# POWER_Management.net
KiCad netlist of a schematic drawn in Altium Designer
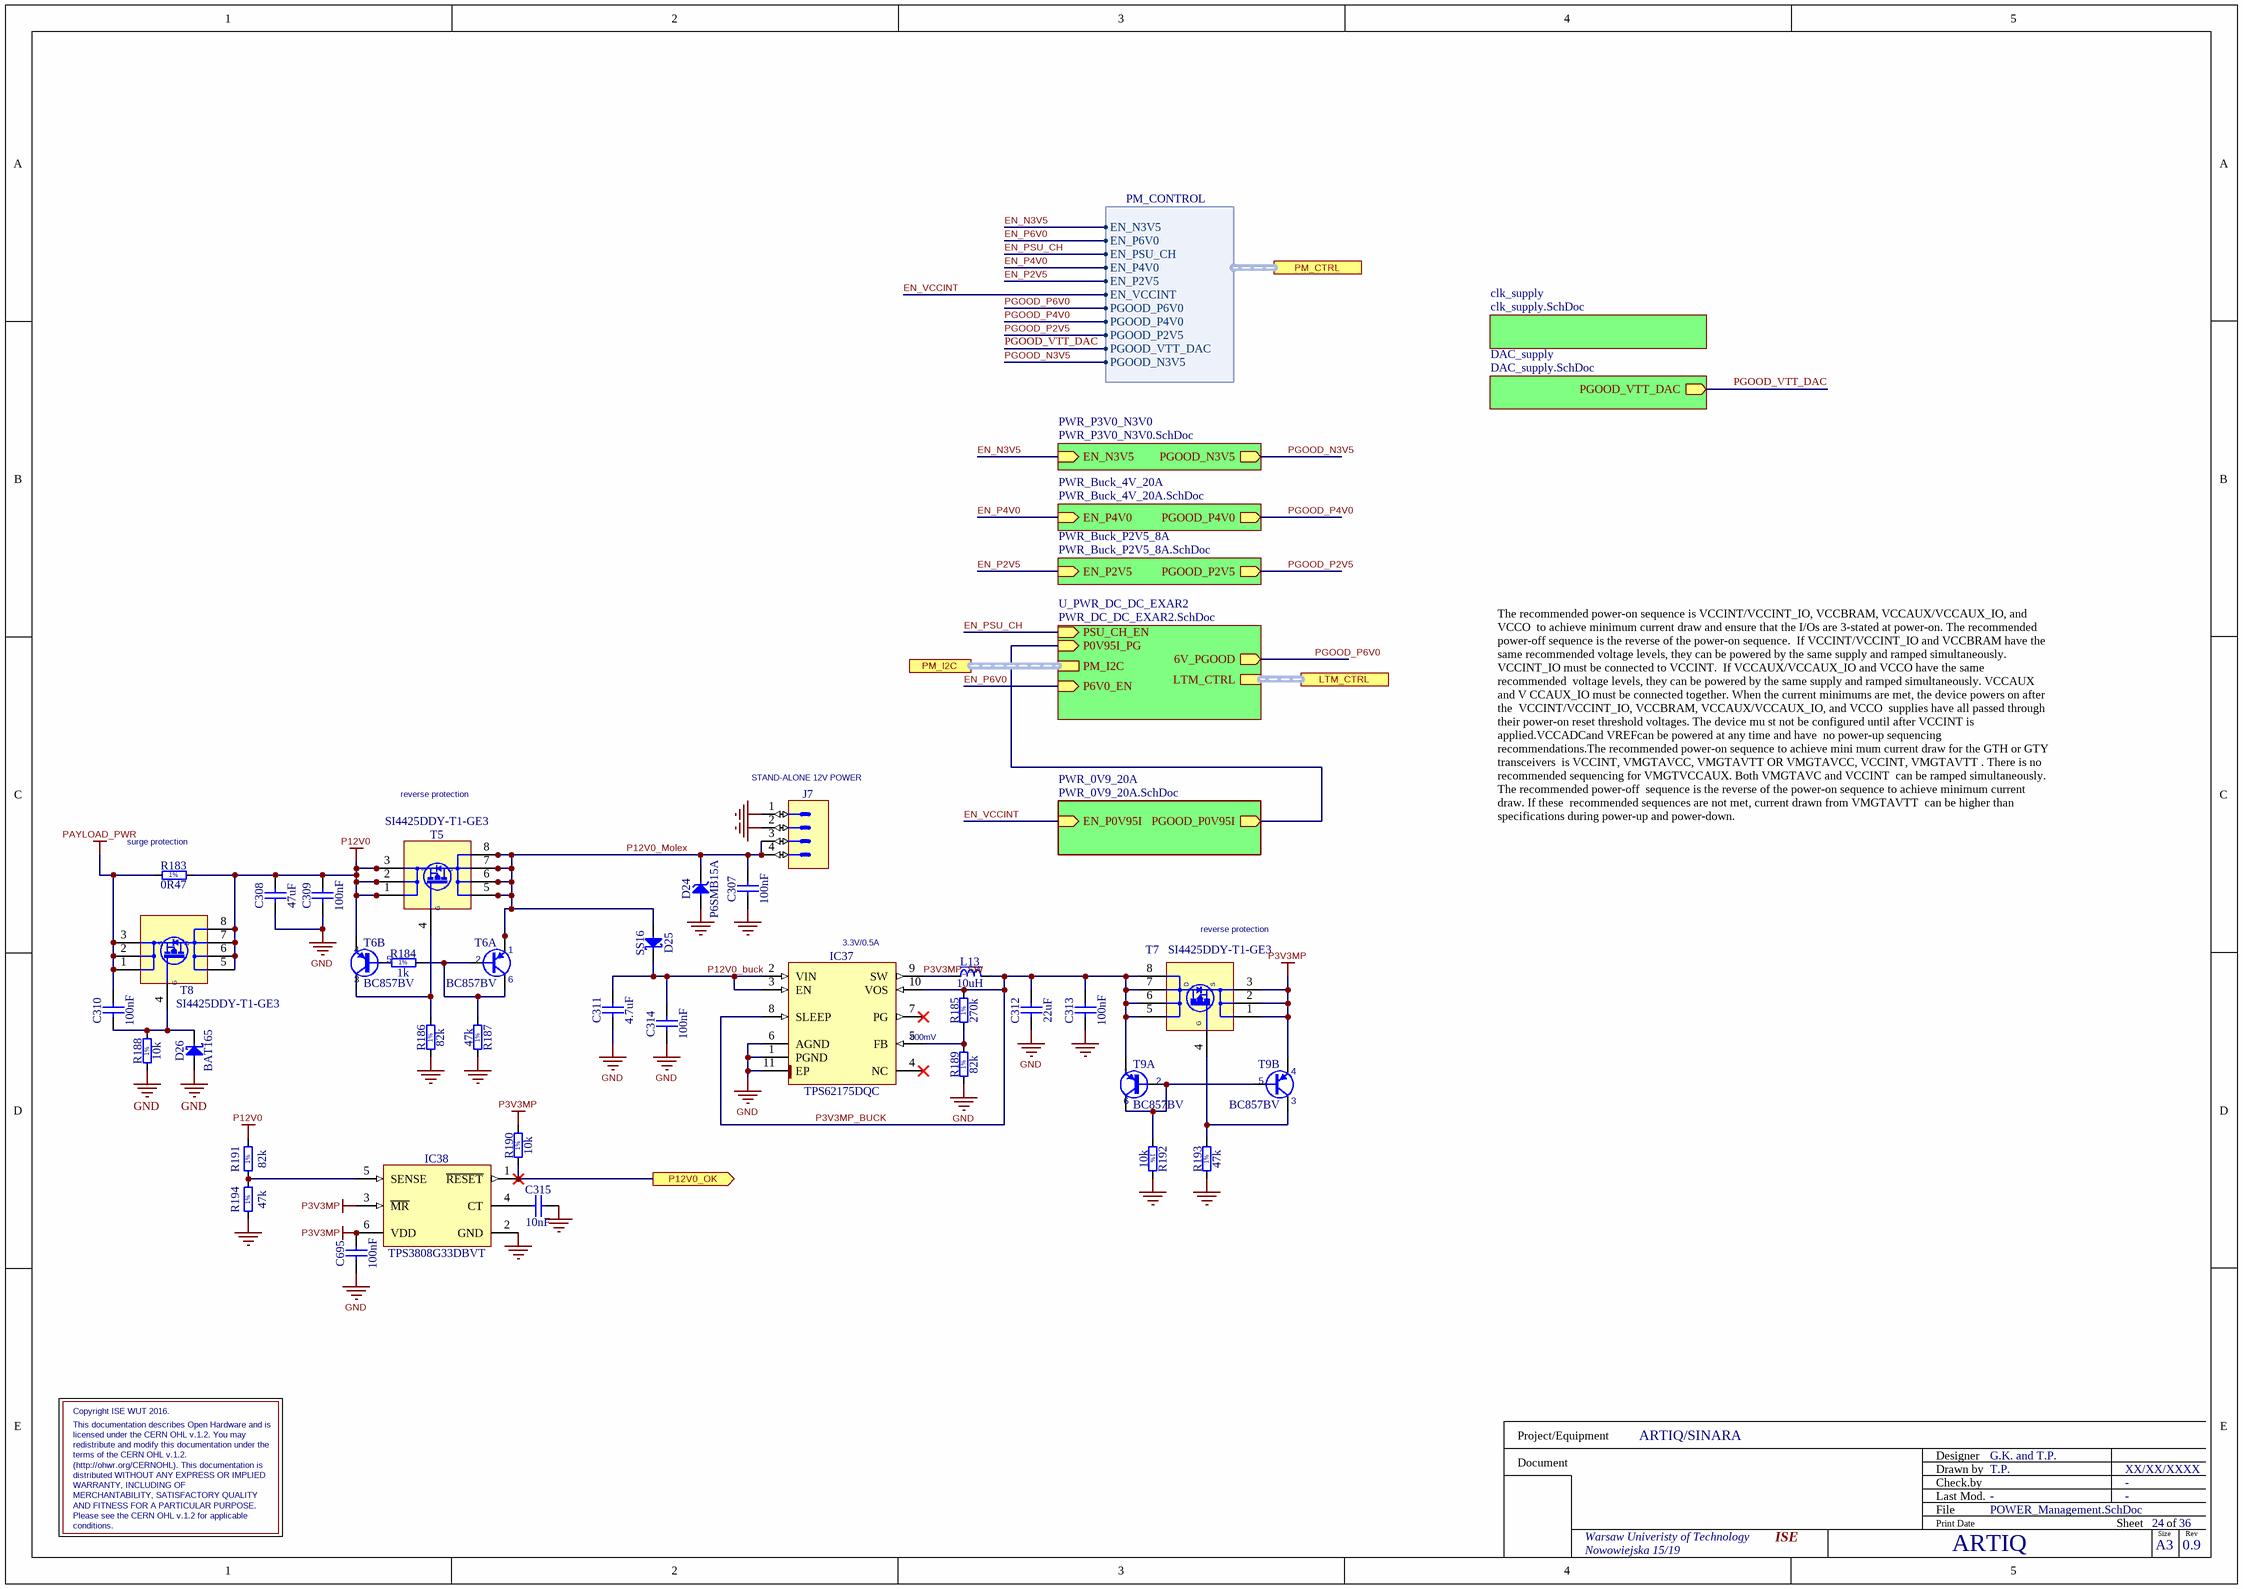
[diagram p0: POWER_Management.SchDoc]

(export (version "E")
  (design (tool "Eeschema 10.0.6"))
  (components
    (comp (ref "C307")
      (value "100nF")
      (footprint "CAPC1005X55N")
      (description "Non-polarised capacitor")
      (fields
        (field (name "MANUFACTURER PART NUMBER") "CC0402_100NF_16V_10%_X5R")
        (field (name "MANUFACTURER") "GENERIC")
        (field (name "AUTHOR") "CERN DEM JLC")
      )
      (libsource (lib "Capacitors") (part "Capacitor - non polarized"))
    )
    (comp (ref "C308")
      (value "47uF")
      (footprint "CAPC3216X180N")
      (description "Non-polarised capacitor")
      (fields
        (field (name "MANUFACTURER PART NUMBER") "CC1206_47UF_25V_20%_X5R")
        (field (name "MANUFACTURER") "GENERIC")
        (field (name "AUTHOR") "CERN DEM JLC")
      )
      (libsource (lib "Capacitors") (part "Capacitor - non polarized"))
    )
    (comp (ref "C309")
      (value "100nF")
      (footprint "CAPC1005X55N")
      (description "Non-polarised capacitor")
      (fields
        (field (name "MANUFACTURER PART NUMBER") "CC0402_100NF_16V_10%_X5R")
        (field (name "MANUFACTURER") "GENERIC")
        (field (name "AUTHOR") "CERN DEM JLC")
      )
      (libsource (lib "Capacitors") (part "Capacitor - non polarized"))
    )
    (comp (ref "C310")
      (value "100nF")
      (footprint "CAPC1005X55N")
      (description "Non-polarised capacitor")
      (fields
        (field (name "MANUFACTURER PART NUMBER") "CC0402_100NF_16V_10%_X5R")
        (field (name "MANUFACTURER") "GENERIC")
        (field (name "AUTHOR") "CERN DEM JLC")
      )
      (libsource (lib "Capacitors") (part "Capacitor - non polarized"))
    )
    (comp (ref "C311")
      (value "4.7uF")
      (footprint "CAPC1709X95N")
      (description "Non-polarised capacitor")
      (fields
        (field (name "MANUFACTURER PART NUMBER") "CC0603_4.7UF_16V_10%_X5R")
        (field (name "MANUFACTURER") "GENERIC")
        (field (name "AUTHOR") "CERN DEM JLC")
      )
      (libsource (lib "Capacitors") (part "Capacitor - non polarized"))
    )
    (comp (ref "C312")
      (value "22uF")
      (footprint "CAPC2012X135N")
      (description "Non-polarised capacitor")
      (fields
        (field (name "MANUFACTURER PART NUMBER") "CC0805_22UF_16V_10%_X5R")
        (field (name "MANUFACTURER") "GENERIC")
        (field (name "AUTHOR") "CERN DEM JLC")
      )
      (libsource (lib "Capacitors") (part "Capacitor - non polarized"))
    )
    (comp (ref "C313")
      (value "100nF")
      (footprint "CAPC1005X55N")
      (description "Non-polarised capacitor")
      (fields
        (field (name "MANUFACTURER PART NUMBER") "CC0402_100NF_16V_10%_X5R")
        (field (name "MANUFACTURER") "GENERIC")
        (field (name "AUTHOR") "CERN DEM JLC")
      )
      (libsource (lib "Capacitors") (part "Capacitor - non polarized"))
    )
    (comp (ref "C314")
      (value "100nF")
      (footprint "CAPC1005X55N")
      (description "Non-polarised capacitor")
      (fields
        (field (name "MANUFACTURER PART NUMBER") "CC0402_100NF_16V_10%_X5R")
        (field (name "MANUFACTURER") "GENERIC")
        (field (name "AUTHOR") "CERN DEM JLC")
      )
      (libsource (lib "Capacitors") (part "Capacitor - non polarized"))
    )
    (comp (ref "C315")
      (value "10nF")
      (footprint "CAPC1005X55N")
      (description "Non-polarised capacitor")
      (fields
        (field (name "MANUFACTURER PART NUMBER") "CC0402_10NF_16V_10%_X7R")
        (field (name "MANUFACTURER") "GENERIC")
        (field (name "AUTHOR") "CERN DEM JLC")
      )
      (libsource (lib "Capacitors") (part "Capacitor - non polarized"))
    )
    (comp (ref "C695")
      (value "100nF")
      (footprint "CAPC1005X55N")
      (description "Non-polarised capacitor")
      (fields
        (field (name "MANUFACTURER PART NUMBER") "CC0402_100NF_16V_10%_X5R")
        (field (name "MANUFACTURER") "GENERIC")
        (field (name "AUTHOR") "CERN DEM JLC")
      )
      (libsource (lib "Capacitors") (part "Capacitor - non polarized"))
    )
    (comp (ref "D24")
      (value "P6SMB15A")
      (footprint "DIOM5436X261N")
      (description "Transient Voltage Suppressor Diode (Uni-Directional)")
      (fields
        (field (name "VOLTAGE") "15V")
        (field (name "POWER") "600W")
        (field (name "AUTHOR") "CERN DEM JLC")
      )
      (libsource (lib "ICs And Semiconductors") (part "Diode TVS Uni-Directional"))
    )
    (comp (ref "D25")
      (value "SS16")
      (footprint "DIOM5127X229N")
      (description "Schottky Diode")
      (fields
        (field (name "MANUFACTURER") "VISHAY GENERAL SEMICONDUCTOR")
        (field (name "VOLTAGE") "60V")
        (field (name "AUTHOR") "CERN DEM JLC")
      )
      (libsource (lib "ICs And Semiconductors") (part "Diode Schottky"))
    )
    (comp (ref "D26")
      (value "BAT165")
      (footprint "SOD2512X110N")
      (description "Schottky Diode")
      (fields
        (field (name "MANUFACTURER") "INFINEON")
        (field (name "VOLTAGE") "40V")
        (field (name "AUTHOR") "CERN DEM JLC")
      )
      (libsource (lib "ICs And Semiconductors") (part "Diode Schottky"))
    )
    (comp (ref "IC37")
      (value "TPS62175DQC")
      (footprint "SON50P200X300X80-11N-R94X250")
      (description "4.75-28VDC to 1-6VDC, 500mA Step-Down Converter With Sleep Mode")
      (fields (field (name "MANUFACTURER") "TEXAS INSTRUMENTS") (field (name "AUTHOR") "CERN DEM JMW"))
      (libsource (lib "ICs And Semiconductors") (part "TPS62175"))
    )
    (comp (ref "IC38")
      (value "TPS3808G33DBVT")
      (footprint "SOT95P280X145-6N")
      (description "Low Quiescent Current, Programmable-Delay Supervisory Circuit")
      (fields (field (name "MANUFACTURER") "TEXAS INSTRUMENTS") (field (name "AUTHOR") "CERN DEM JLC"))
      (libsource (lib "ICs And Semiconductors") (part "TPS3808xxxDBV"))
    )
    (comp (ref "J7")
      (value "Mini-Fit Jr.™")
      (footprint "MOLEX_39-28-1043")
      (description "Connector 4 Male")
      (fields
        (field (name "MANUFACTURER PART NUMBER") "39-28-1043")
        (field (name "MANUFACTURER") "MOLEX")
        (field (name "AUTHOR") "CERN DEM JLC")
      )
      (libsource (lib "Connectors") (part "Connector 4 Male"))
    )
    (comp (ref "L13")
      (value "10uH")
      (footprint "IND_MURATA-PS_8400")
      (description "Inductor With Core")
      (fields
        (field (name "MANUFACTURER PART NUMBER") "84103C")
        (field (name "MANUFACTURER") "MURATA POWER SOLUTIONS")
        (field (name "AUTHOR") "CERN DEM JLC")
      )
      (libsource (lib "Inductors & Transformers") (part "Inductor With Magnetic core"))
    )
    (comp (ref "R183")
      (value "0R47")
      (footprint "RESC3216X65N")
      (description "Resistor - 1%")
      (fields
        (field (name "PART NUMBER") "R1206_0R47_1%_0.5W_600PPM")
        (field (name "POWER") "0.5W")
        (field (name "AUTHOR") "CERN DEM JLC")
      )
      (libsource (lib "Resistors") (part "Resistor - 1%"))
    )
    (comp (ref "R184")
      (value "1k")
      (footprint "RESC1005X40N")
      (description "Resistor - 1%")
      (fields
        (field (name "MANUFACTURER PART NUMBER") "R0402_1K_1%_0.0625W_100PPM")
        (field (name "MANUFACTURER") "GENERIC")
        (field (name "AUTHOR") "CERN DEM JLC")
      )
      (libsource (lib "Resistors") (part "Resistor - 1%"))
    )
    (comp (ref "R185")
      (value "270k")
      (footprint "RESC1005X40N")
      (description "Resistor - 1%")
      (fields
        (field (name "MANUFACTURER PART NUMBER") "R0402_270K_1%_0.0625W_100PPM")
        (field (name "MANUFACTURER") "GENERIC")
        (field (name "AUTHOR") "CERN DEM JLC")
      )
      (libsource (lib "Resistors") (part "Resistor - 1%"))
    )
    (comp (ref "R186")
      (value "82k")
      (footprint "RESC1005X40N")
      (description "Resistor - 1%")
      (fields
        (field (name "MANUFACTURER PART NUMBER") "R0402_82K_1%_0.0625W_100PPM")
        (field (name "MANUFACTURER") "GENERIC")
        (field (name "AUTHOR") "CERN DEM JLC")
      )
      (libsource (lib "Resistors") (part "Resistor - 1%"))
    )
    (comp (ref "R187")
      (value "47k")
      (footprint "RESC1005X40N")
      (description "Resistor - 1%")
      (fields
        (field (name "MANUFACTURER PART NUMBER") "R0402_47K_1%_0.0625W_100PPM")
        (field (name "MANUFACTURER") "GENERIC")
        (field (name "AUTHOR") "CERN DEM JLC")
      )
      (libsource (lib "Resistors") (part "Resistor - 1%"))
    )
    (comp (ref "R188")
      (value "10k")
      (footprint "RESC1005X40N")
      (description "Resistor - 1%")
      (fields
        (field (name "MANUFACTURER PART NUMBER") "R0402_10K_1%_0.0625W_100PPM")
        (field (name "MANUFACTURER") "GENERIC")
        (field (name "AUTHOR") "CERN DEM JLC")
      )
      (libsource (lib "Resistors") (part "Resistor - 1%"))
    )
    (comp (ref "R189")
      (value "82k")
      (footprint "RESC1005X40N")
      (description "Resistor - 1%")
      (fields
        (field (name "MANUFACTURER PART NUMBER") "R0402_82K_1%_0.0625W_100PPM")
        (field (name "MANUFACTURER") "GENERIC")
        (field (name "AUTHOR") "CERN DEM JLC")
      )
      (libsource (lib "Resistors") (part "Resistor - 1%"))
    )
    (comp (ref "R190")
      (value "10k")
      (footprint "RESC1005X40N")
      (description "Resistor - 1%")
      (fields
        (field (name "MANUFACTURER PART NUMBER") "R0402_10K_1%_0.0625W_100PPM")
        (field (name "MANUFACTURER") "GENERIC")
        (field (name "AUTHOR") "CERN DEM JLC")
      )
      (libsource (lib "Resistors") (part "Resistor - 1%"))
    )
    (comp (ref "R191")
      (value "82k")
      (footprint "RESC1005X40N")
      (description "Resistor - 1%")
      (fields
        (field (name "MANUFACTURER PART NUMBER") "R0402_82K_1%_0.0625W_100PPM")
        (field (name "MANUFACTURER") "GENERIC")
        (field (name "AUTHOR") "CERN DEM JLC")
      )
      (libsource (lib "Resistors") (part "Resistor - 1%"))
    )
    (comp (ref "R192")
      (value "10k")
      (footprint "RESC1005X40N")
      (description "Resistor - 1%")
      (fields
        (field (name "MANUFACTURER PART NUMBER") "R0402_10K_1%_0.0625W_100PPM")
        (field (name "MANUFACTURER") "GENERIC")
        (field (name "AUTHOR") "CERN DEM JLC")
      )
      (libsource (lib "Resistors") (part "Resistor - 1%"))
    )
    (comp (ref "R193")
      (value "47k")
      (footprint "RESC1005X40N")
      (description "Resistor - 1%")
      (fields
        (field (name "MANUFACTURER PART NUMBER") "R0402_47K_1%_0.0625W_100PPM")
        (field (name "MANUFACTURER") "GENERIC")
        (field (name "AUTHOR") "CERN DEM JLC")
      )
      (libsource (lib "Resistors") (part "Resistor - 1%"))
    )
    (comp (ref "R194")
      (value "47k")
      (footprint "RESC1005X40N")
      (description "Resistor - 1%")
      (fields
        (field (name "MANUFACTURER PART NUMBER") "R0402_47K_1%_0.0625W_100PPM")
        (field (name "MANUFACTURER") "GENERIC")
        (field (name "AUTHOR") "CERN DEM JLC")
      )
      (libsource (lib "Resistors") (part "Resistor - 1%"))
    )
    (comp (ref "T5")
      (value "SI4425DDY-T1-GE3")
      (footprint "SOIC127P600X175-8N")
      (description "-30V -19.7A P-Channel MOSFET")
      (fields (field (name "MANUFACTURER") "VISHAY SILICONIX") (field (name "AUTHOR") "CERN DEM MR"))
      (libsource (lib "ICs And Semiconductors") (part "SI4425DDY"))
    )
    (comp (ref "T6")
      (value "BC857BV")
      (footprint "SOTFL50P160X60-6N")
      (description "45V, 100mA PNP General Purpose Double Transistor")
      (fields (field (name "MANUFACTURER") "NXP SEMICONDUCTORS") (field (name "AUTHOR") "CERN DEM JLC"))
      (libsource (lib "") (part "BC857BV_1"))
    )
    (comp (ref "T7")
      (value "SI4425DDY-T1-GE3")
      (footprint "SOIC127P600X175-8N")
      (description "-30V -19.7A P-Channel MOSFET")
      (fields (field (name "MANUFACTURER") "VISHAY SILICONIX") (field (name "AUTHOR") "CERN DEM MR"))
      (libsource (lib "") (part "SI4425DDY_1"))
    )
    (comp (ref "T8")
      (value "SI4425DDY-T1-GE3")
      (footprint "SOIC127P600X175-8N")
      (description "-30V -19.7A P-Channel MOSFET")
      (fields (field (name "MANUFACTURER") "VISHAY SILICONIX") (field (name "AUTHOR") "CERN DEM MR"))
      (libsource (lib "ICs And Semiconductors") (part "SI4425DDY"))
    )
    (comp (ref "T9")
      (value "BC857BV")
      (footprint "SOTFL50P160X60-6N")
      (description "45V, 100mA PNP General Purpose Double Transistor")
      (fields (field (name "MANUFACTURER") "NXP SEMICONDUCTORS") (field (name "AUTHOR") "CERN DEM JLC"))
      (libsource (lib "") (part "BC857BV_1"))
    )
  )
  (nets
    (net (code "11") (name "/P3V3MP_BUCK") (class "Default")
      (node (ref "C312") (pin "2") (pinfunction "2_2") (pintype "passive"))
      (node (ref "C313") (pin "2") (pinfunction "2_2") (pintype "passive"))
      (node (ref "IC37") (pin "10") (pinfunction "VOS_10") (pintype "input"))
      (node (ref "IC37") (pin "8") (pinfunction "SLEEP_8") (pintype "input"))
      (node (ref "L13") (pin "2") (pinfunction "2_2") (pintype "passive"))
      (node (ref "R185") (pin "2") (pinfunction "2_2") (pintype "passive"))
      (node (ref "T7") (pin "5") (pinfunction "D_5") (pintype "passive"))
      (node (ref "T7") (pin "6") (pinfunction "D_6") (pintype "passive"))
      (node (ref "T7") (pin "7") (pinfunction "D_7") (pintype "passive"))
      (node (ref "T7") (pin "8") (pinfunction "D_8") (pintype "passive"))
      (node (ref "T9") (pin "1") (pinfunction "E_1") (pintype "passive"))
    )
    (net (code "12") (name "/P3V3MP_SW") (class "Default")
      (node (ref "IC37") (pin "9") (pinfunction "SW_9") (pintype "output"))
      (node (ref "L13") (pin "1") (pinfunction "1_1") (pintype "passive"))
    )
    (net (code "13") (name "/P12V0_Molex") (class "Default")
      (node (ref "C307") (pin "2") (pinfunction "2_2") (pintype "passive"))
      (node (ref "D24") (pin "1") (pinfunction "C_1") (pintype "passive"))
      (node (ref "D25") (pin "2") (pinfunction "A_2") (pintype "passive"))
      (node (ref "J7") (pin "3") (pinfunction "3_3") (pintype "bidirectional"))
      (node (ref "J7") (pin "4") (pinfunction "4_4") (pintype "bidirectional"))
      (node (ref "T5") (pin "5") (pinfunction "D_5") (pintype "passive"))
      (node (ref "T5") (pin "6") (pinfunction "D_6") (pintype "passive"))
      (node (ref "T5") (pin "7") (pinfunction "D_7") (pintype "passive"))
      (node (ref "T5") (pin "8") (pinfunction "D_8") (pintype "passive"))
      (node (ref "T6") (pin "1") (pinfunction "E_1") (pintype "passive"))
    )
    (net (code "14") (name "/P12V0_OK") (class "Default")
      (node (ref "IC38") (pin "1") (pinfunction "~{RESET}_1") (pintype "output"))
      (node (ref "R190") (pin "1") (pinfunction "1_1") (pintype "passive"))
    )
    (net (code "15") (name "/P12V0_buck") (class "Default")
      (node (ref "C311") (pin "2") (pinfunction "2_2") (pintype "passive"))
      (node (ref "C314") (pin "2") (pinfunction "2_2") (pintype "passive"))
      (node (ref "D25") (pin "1") (pinfunction "C_1") (pintype "passive"))
      (node (ref "IC37") (pin "2") (pinfunction "VIN_2") (pintype "input"))
      (node (ref "IC37") (pin "3") (pinfunction "EN_3") (pintype "input"))
    )
    (net (code "24") (name "GND") (class "Default")
      (node (ref "C307") (pin "1") (pinfunction "1_1") (pintype "passive"))
      (node (ref "C308") (pin "1") (pinfunction "1_1") (pintype "passive"))
      (node (ref "C309") (pin "1") (pinfunction "1_1") (pintype "passive"))
      (node (ref "C311") (pin "1") (pinfunction "1_1") (pintype "passive"))
      (node (ref "C312") (pin "1") (pinfunction "1_1") (pintype "passive"))
      (node (ref "C313") (pin "1") (pinfunction "1_1") (pintype "passive"))
      (node (ref "C314") (pin "1") (pinfunction "1_1") (pintype "passive"))
      (node (ref "C315") (pin "1") (pinfunction "1_1") (pintype "passive"))
      (node (ref "C695") (pin "1") (pinfunction "1_1") (pintype "passive"))
      (node (ref "D24") (pin "2") (pinfunction "A_2") (pintype "passive"))
      (node (ref "D26") (pin "2") (pinfunction "A_2") (pintype "passive"))
      (node (ref "IC37") (pin "1") (pinfunction "PGND_1") (pintype "power_in"))
      (node (ref "IC37") (pin "11") (pinfunction "EP_11") (pintype "power_in"))
      (node (ref "IC37") (pin "6") (pinfunction "AGND_6") (pintype "power_in"))
      (node (ref "IC38") (pin "2") (pinfunction "GND_2") (pintype "power_in"))
      (node (ref "J7") (pin "1") (pinfunction "1_1") (pintype "bidirectional"))
      (node (ref "J7") (pin "2") (pinfunction "2_2") (pintype "bidirectional"))
      (node (ref "R186") (pin "1") (pinfunction "1_1") (pintype "passive"))
      (node (ref "R187") (pin "1") (pinfunction "1_1") (pintype "passive"))
      (node (ref "R188") (pin "1") (pinfunction "1_1") (pintype "passive"))
      (node (ref "R189") (pin "1") (pinfunction "1_1") (pintype "passive"))
      (node (ref "R192") (pin "2") (pinfunction "2_2") (pintype "passive"))
      (node (ref "R193") (pin "1") (pinfunction "1_1") (pintype "passive"))
      (node (ref "R194") (pin "1") (pinfunction "1_1") (pintype "passive"))
    )
    (net (code "25") (name "Net-(D26-C)") (class "Default")
      (node (ref "C310") (pin "1") (pinfunction "1_1") (pintype "passive"))
      (node (ref "D26") (pin "1") (pinfunction "C_1") (pintype "passive"))
      (node (ref "R188") (pin "2") (pinfunction "2_2") (pintype "passive"))
      (node (ref "T8") (pin "4") (pinfunction "S_4") (pintype "passive"))
    )
    (net (code "26") (name "Net-(IC37-FB)") (class "Default")
      (node (ref "IC37") (pin "5") (pinfunction "FB_5") (pintype "input"))
      (node (ref "R185") (pin "1") (pinfunction "1_1") (pintype "passive"))
      (node (ref "R189") (pin "2") (pinfunction "2_2") (pintype "passive"))
    )
    (net (code "27") (name "Net-(IC38-CT)") (class "Default")
      (node (ref "C315") (pin "2") (pinfunction "2_2") (pintype "passive"))
      (node (ref "IC38") (pin "4") (pinfunction "CT_4") (pintype "passive"))
    )
    (net (code "28") (name "Net-(IC38-SENSE)") (class "Default")
      (node (ref "IC38") (pin "5") (pinfunction "SENSE_5") (pintype "input"))
      (node (ref "R191") (pin "1") (pinfunction "1_1") (pintype "passive"))
      (node (ref "R194") (pin "2") (pinfunction "2_2") (pintype "passive"))
    )
    (net (code "29") (name "Net-(T6A-B)") (class "Default")
      (node (ref "R184") (pin "2") (pinfunction "2_2") (pintype "passive"))
      (node (ref "R187") (pin "2") (pinfunction "2_2") (pintype "passive"))
      (node (ref "T6") (pin "2") (pinfunction "B_2") (pintype "passive"))
      (node (ref "T6") (pin "6") (pinfunction "C_6") (pintype "passive"))
    )
    (net (code "30") (name "Net-(T6B-B)") (class "Default")
      (node (ref "R184") (pin "1") (pinfunction "1_1") (pintype "passive"))
      (node (ref "T6") (pin "5") (pinfunction "B_5") (pintype "passive"))
    )
    (net (code "31") (name "Net-(T6B-C)") (class "Default")
      (node (ref "R186") (pin "2") (pinfunction "2_2") (pintype "passive"))
      (node (ref "T5") (pin "4") (pinfunction "S_4") (pintype "passive"))
      (node (ref "T6") (pin "3") (pinfunction "C_3") (pintype "passive"))
    )
    (net (code "32") (name "Net-(T9A-B)") (class "Default")
      (node (ref "R192") (pin "1") (pinfunction "1_1") (pintype "passive"))
      (node (ref "T9") (pin "2") (pinfunction "B_2") (pintype "passive"))
      (node (ref "T9") (pin "5") (pinfunction "B_5") (pintype "passive"))
      (node (ref "T9") (pin "6") (pinfunction "C_6") (pintype "passive"))
    )
    (net (code "33") (name "Net-(T9B-C)") (class "Default")
      (node (ref "R193") (pin "2") (pinfunction "2_2") (pintype "passive"))
      (node (ref "T7") (pin "4") (pinfunction "S_4") (pintype "passive"))
      (node (ref "T9") (pin "3") (pinfunction "C_3") (pintype "passive"))
    )
    (net (code "34") (name "P3V3MP") (class "Default")
      (node (ref "C695") (pin "2") (pinfunction "2_2") (pintype "passive"))
      (node (ref "IC38") (pin "3") (pinfunction "~{MR}_3") (pintype "input"))
      (node (ref "IC38") (pin "6") (pinfunction "VDD_6") (pintype "power_in"))
      (node (ref "R190") (pin "2") (pinfunction "2_2") (pintype "passive"))
      (node (ref "T7") (pin "1") (pinfunction "S_1") (pintype "passive"))
      (node (ref "T7") (pin "2") (pinfunction "S_2") (pintype "passive"))
      (node (ref "T7") (pin "3") (pinfunction "S_3") (pintype "passive"))
      (node (ref "T9") (pin "4") (pinfunction "E_4") (pintype "passive"))
    )
    (net (code "35") (name "P12V0") (class "Default")
      (node (ref "C308") (pin "2") (pinfunction "2_2") (pintype "passive"))
      (node (ref "C309") (pin "2") (pinfunction "2_2") (pintype "passive"))
      (node (ref "R183") (pin "2") (pinfunction "2_2") (pintype "passive"))
      (node (ref "R191") (pin "2") (pinfunction "2_2") (pintype "passive"))
      (node (ref "T5") (pin "1") (pinfunction "S_1") (pintype "passive"))
      (node (ref "T5") (pin "2") (pinfunction "S_2") (pintype "passive"))
      (node (ref "T5") (pin "3") (pinfunction "S_3") (pintype "passive"))
      (node (ref "T6") (pin "4") (pinfunction "E_4") (pintype "passive"))
      (node (ref "T8") (pin "5") (pinfunction "D_5") (pintype "passive"))
      (node (ref "T8") (pin "6") (pinfunction "D_6") (pintype "passive"))
      (node (ref "T8") (pin "7") (pinfunction "D_7") (pintype "passive"))
      (node (ref "T8") (pin "8") (pinfunction "D_8") (pintype "passive"))
    )
    (net (code "36") (name "PAYLOAD_PWR") (class "Default")
      (node (ref "C310") (pin "2") (pinfunction "2_2") (pintype "passive"))
      (node (ref "R183") (pin "1") (pinfunction "1_1") (pintype "passive"))
      (node (ref "T8") (pin "1") (pinfunction "S_1") (pintype "passive"))
      (node (ref "T8") (pin "2") (pinfunction "S_2") (pintype "passive"))
      (node (ref "T8") (pin "3") (pinfunction "S_3") (pintype "passive"))
    )
    (net (code "37") (name "unconnected-(IC37-NC-Pad4)") (class "Default")
      (node (ref "IC37") (pin "4") (pinfunction "NC_4") (pintype "passive+no_connect"))
    )
    (net (code "38") (name "unconnected-(IC37-PG-Pad7)") (class "Default")
      (node (ref "IC37") (pin "7") (pinfunction "PG_7") (pintype "output+no_connect"))
    )
  )
)
